# Accelerometer.net
KiCad netlist of a schematic drawn in Altium Designer
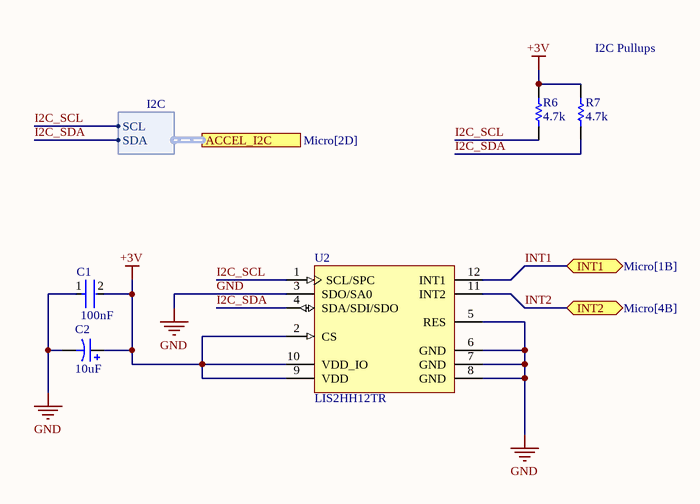
[diagram p0: Accelerometer.SchDoc]

(export (version "E")
  (design (tool "Eeschema 10.0.6"))
  (components
    (comp (ref "C1")
      (value "100nF")
      (footprint "FP-C0402-BB-MFG")
      (description "CAP CER 0.1UF 10V X5R 0402")
      (fields (field (name "MANUFACTURER") "Kemet") (field (name "TOLERANCE") "0.1"))
      (libsource (lib "Altium Content Vault") (part "b4654b650e69147ec39a6b967a45e02"))
    )
    (comp (ref "C2")
      (value "10uF")
      (footprint "C0805")
      (description "Alum. Electrolytic Cap 10µF 50V; 5mm Surface Mount; Lifetime 2000h; +105°C")
      (fields
        (field (name "MANUFACTURER") "Wurth Electronics")
        (field (name "MANUFACTURER PART NUMBER") "865080642006")
        (field (name "PUBLISHER") "Altium Limited")
      )
      (libsource (lib "Miscellaneous Devices") (part "Cap Pol3"))
    )
    (comp (ref "R6")
      (value "4.7k")
      (footprint "RESC1608X55X30NL15T15")
      (fields (field (name "TOLERANCE") "5%"))
      (libsource (lib "Altium Content Vault") (part "RES-2"))
    )
    (comp (ref "R7")
      (value "4.7k")
      (footprint "RESC1608X55X30NL15T15")
      (fields (field (name "TOLERANCE") "5%"))
      (libsource (lib "Altium Content Vault") (part "RES-2"))
    )
    (comp (ref "U2")
      (value "LIS2HH12TR")
      (footprint "STM-LGA-12")
      (fields (field (name "MANUFACTURER") "STMicroelectronics"))
      (libsource (lib "Altium Content Vault") (part "STM-LIS2HH12-LGA-12"))
    )
  )
  (nets
    (net (code "2") (name "+3V") (class "Default")
      (node (ref "C1") (pin "2") (pinfunction "2_2") (pintype "passive"))
      (node (ref "C2") (pin "1") (pinfunction "1_1") (pintype "passive"))
      (node (ref "R6") (pin "2") (pinfunction "2_2") (pintype "passive"))
      (node (ref "R7") (pin "2") (pinfunction "2_2") (pintype "passive"))
      (node (ref "U2") (pin "10") (pinfunction "VDD_IO_10") (pintype "power_in"))
      (node (ref "U2") (pin "2") (pinfunction "CS_2") (pintype "input"))
      (node (ref "U2") (pin "9") (pinfunction "VDD_9") (pintype "power_in"))
    )
    (net (code "3") (name "/I2C_SCL") (class "Default")
      (node (ref "R6") (pin "1") (pinfunction "1_1") (pintype "passive"))
      (node (ref "U2") (pin "1") (pinfunction "SCL/SPC_1") (pintype "input"))
    )
    (net (code "4") (name "/I2C_SDA") (class "Default")
      (node (ref "R7") (pin "1") (pinfunction "1_1") (pintype "passive"))
      (node (ref "U2") (pin "4") (pinfunction "SDA/SDI/SDO_4") (pintype "bidirectional"))
    )
    (net (code "5") (name "/INT1") (class "Default")
      (node (ref "U2") (pin "12") (pinfunction "INT1_12") (pintype "passive"))
    )
    (net (code "6") (name "/INT2") (class "Default")
      (node (ref "U2") (pin "11") (pinfunction "INT2_11") (pintype "passive"))
    )
    (net (code "8") (name "GND") (class "Default")
      (node (ref "C1") (pin "1") (pinfunction "1_1") (pintype "passive"))
      (node (ref "C2") (pin "2") (pinfunction "2_2") (pintype "passive"))
      (node (ref "U2") (pin "3") (pinfunction "SDO/SA0_3") (pintype "passive"))
      (node (ref "U2") (pin "5") (pinfunction "RES_5") (pintype "passive"))
      (node (ref "U2") (pin "6") (pinfunction "GND_6") (pintype "power_in"))
      (node (ref "U2") (pin "7") (pinfunction "GND_7") (pintype "power_in"))
      (node (ref "U2") (pin "8") (pinfunction "GND_8") (pintype "power_in"))
    )
  )
)
